# SlaveV1.net
KiCad netlist of a schematic drawn in EAGLE
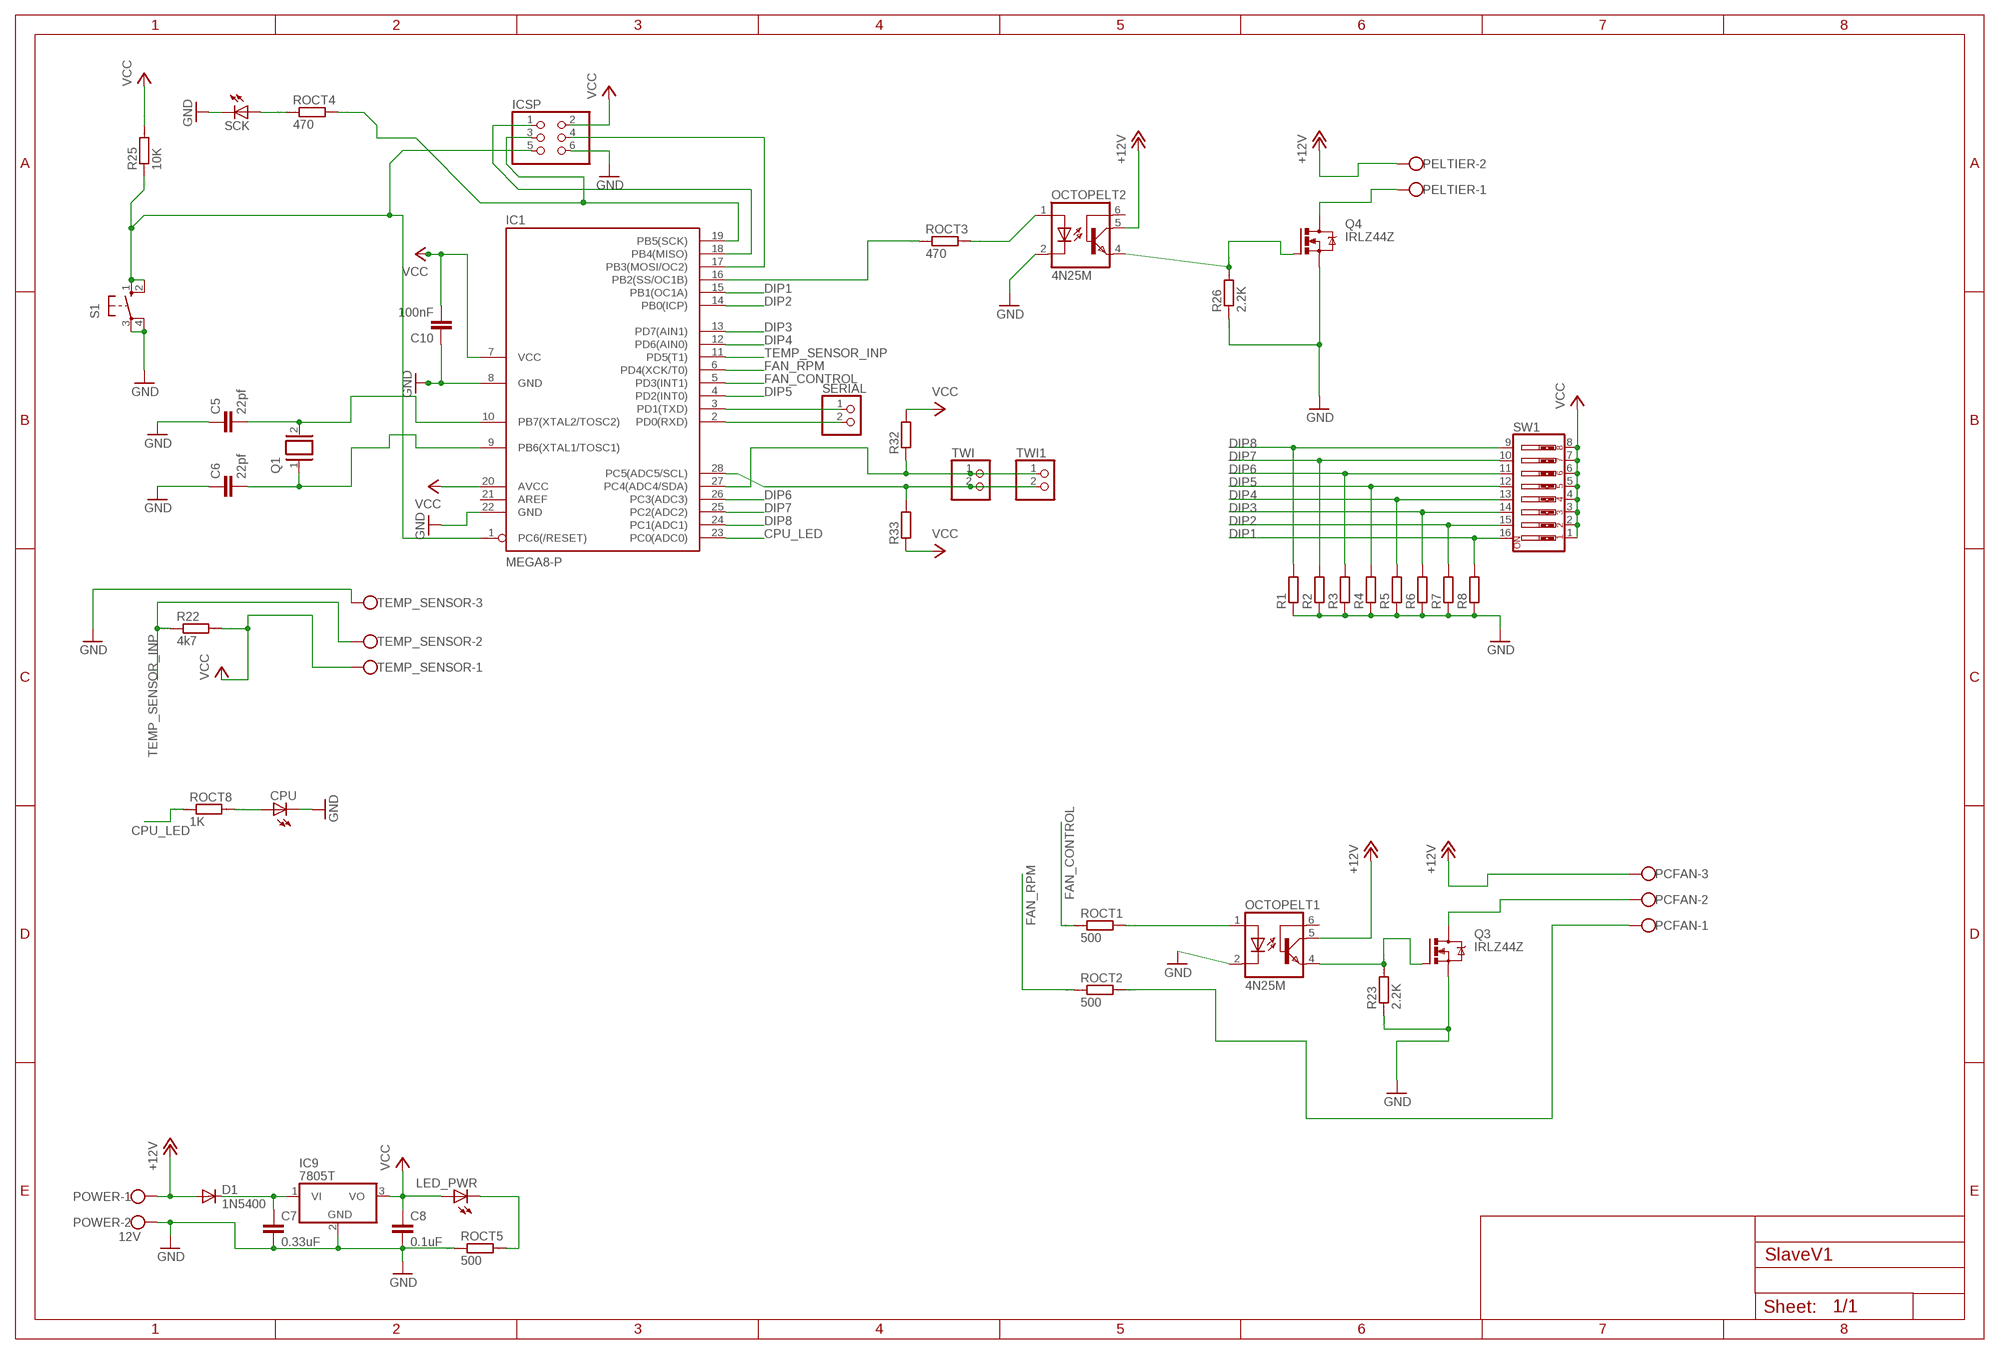
[diagram p0: schematic, sheet 1]

(export (version "E")
  (design (tool "Eeschema 10.0.6"))
  (components
    (comp (ref "C5")
      (value "22pf")
      (footprint "eagle-import:C2.5-3")
      (libsource (lib "eagle-import") (part "C2,5-3"))
    )
    (comp (ref "C6")
      (value "22pf")
      (footprint "eagle-import:C2.5-3")
      (libsource (lib "eagle-import") (part "C2,5-3"))
    )
    (comp (ref "C7")
      (value "0.33uF")
      (footprint "eagle-import:C2.5-3")
      (libsource (lib "eagle-import") (part "C2,5-3"))
    )
    (comp (ref "C8")
      (value "0.1uF")
      (footprint "eagle-import:C2.5-3")
      (libsource (lib "eagle-import") (part "C2,5-3"))
    )
    (comp (ref "C10")
      (value "100nF")
      (footprint "eagle-import:C2.5-3")
      (libsource (lib "eagle-import") (part "C2,5-3"))
    )
    (comp (ref "CPU")
      (value "LED5MM")
      (footprint "eagle-import:LED5MM")
      (libsource (lib "eagle-import") (part "LED5MM"))
    )
    (comp (ref "D1")
      (value "1N5400")
      (footprint "eagle-import:DO201-15")
      (libsource (lib "eagle-import") (part "1N5400"))
    )
    (comp (ref "IC1")
      (value "MEGA8-P")
      (footprint "eagle-import:DIL28-3")
      (libsource (lib "eagle-import") (part "MEGA8-P"))
    )
    (comp (ref "IC9")
      (value "7805T")
      (footprint "eagle-import:TO220H")
      (libsource (lib "eagle-import") (part "78T05"))
    )
    (comp (ref "ICSP")
      (value "PINHD-2X3")
      (footprint "eagle-import:2X03")
      (libsource (lib "eagle-import") (part "PINHD-2X3"))
    )
    (comp (ref "LED_PWR")
      (value "LED5MM")
      (footprint "eagle-import:LED5MM")
      (libsource (lib "eagle-import") (part "LED5MM"))
    )
    (comp (ref "OCTOPELT1")
      (value "4N25M")
      (footprint "eagle-import:DIL06")
      (fields (field (name "MPN") "4N25-M"))
      (libsource (lib "eagle-import") (part "4N?M25"))
    )
    (comp (ref "OCTOPELT2")
      (value "4N25M")
      (footprint "eagle-import:DIL06")
      (fields (field (name "MPN") "4N25-M"))
      (libsource (lib "eagle-import") (part "4N?M25"))
    )
    (comp (ref "PCFAN")
      (value "W237-103")
      (footprint "eagle-import:W237-103")
      (fields (field (name "MPN") "237-103"))
      (libsource (lib "eagle-import") (part "W237-103"))
    )
    (comp (ref "PELTIER")
      (value "W237-102")
      (footprint "eagle-import:W237-102")
      (fields (field (name "MPN") "237-102"))
      (libsource (lib "eagle-import") (part "W237-102"))
    )
    (comp (ref "POWER")
      (value "12V")
      (footprint "eagle-import:W237-102")
      (fields (field (name "MPN") "237-102"))
      (libsource (lib "eagle-import") (part "W237-102"))
    )
    (comp (ref "Q1")
      (value "XTAL")
      (footprint "eagle-import:Q")
      (libsource (lib "eagle-import") (part "XTAL"))
    )
    (comp (ref "Q3")
      (value "IRLZ44Z")
      (footprint "eagle-import:TO220BH")
      (libsource (lib "eagle-import") (part "IRLZ44Z"))
    )
    (comp (ref "Q4")
      (value "IRLZ44Z")
      (footprint "eagle-import:TO220BH")
      (libsource (lib "eagle-import") (part "IRLZ44Z"))
    )
    (comp (ref "R1")
      (value "R-EU_0207/10")
      (footprint "eagle-import:0207_10")
      (libsource (lib "eagle-import") (part "R-EU_0207/10"))
    )
    (comp (ref "R2")
      (value "R-EU_0207/10")
      (footprint "eagle-import:0207_10")
      (libsource (lib "eagle-import") (part "R-EU_0207/10"))
    )
    (comp (ref "R3")
      (value "R-EU_0207/10")
      (footprint "eagle-import:0207_10")
      (libsource (lib "eagle-import") (part "R-EU_0207/10"))
    )
    (comp (ref "R4")
      (value "R-EU_0207/10")
      (footprint "eagle-import:0207_10")
      (libsource (lib "eagle-import") (part "R-EU_0207/10"))
    )
    (comp (ref "R5")
      (value "R-EU_0207/10")
      (footprint "eagle-import:0207_10")
      (libsource (lib "eagle-import") (part "R-EU_0207/10"))
    )
    (comp (ref "R6")
      (value "R-EU_0207/10")
      (footprint "eagle-import:0207_10")
      (libsource (lib "eagle-import") (part "R-EU_0207/10"))
    )
    (comp (ref "R7")
      (value "R-EU_0207/10")
      (footprint "eagle-import:0207_10")
      (libsource (lib "eagle-import") (part "R-EU_0207/10"))
    )
    (comp (ref "R8")
      (value "R-EU_0207/10")
      (footprint "eagle-import:0207_10")
      (libsource (lib "eagle-import") (part "R-EU_0207/10"))
    )
    (comp (ref "R22")
      (value "4k7")
      (footprint "eagle-import:0204_7")
      (libsource (lib "eagle-import") (part "R0204/7"))
    )
    (comp (ref "R23")
      (value "2.2K")
      (footprint "eagle-import:0204_7")
      (libsource (lib "eagle-import") (part "R0204/7"))
    )
    (comp (ref "R25")
      (value "10K")
      (footprint "eagle-import:0204_7")
      (libsource (lib "eagle-import") (part "R0204/7"))
    )
    (comp (ref "R26")
      (value "2.2K")
      (footprint "eagle-import:0204_7")
      (libsource (lib "eagle-import") (part "R0204/7"))
    )
    (comp (ref "R32")
      (value "R-EU_0207/10")
      (footprint "eagle-import:0207_10")
      (libsource (lib "eagle-import") (part "R-EU_0207/10"))
    )
    (comp (ref "R33")
      (value "R-EU_0207/10")
      (footprint "eagle-import:0207_10")
      (libsource (lib "eagle-import") (part "R-EU_0207/10"))
    )
    (comp (ref "ROCT1")
      (value "500")
      (footprint "eagle-import:0204_7")
      (libsource (lib "eagle-import") (part "R0204/7"))
    )
    (comp (ref "ROCT2")
      (value "500")
      (footprint "eagle-import:0204_7")
      (libsource (lib "eagle-import") (part "R0204/7"))
    )
    (comp (ref "ROCT3")
      (value "470")
      (footprint "eagle-import:0204_7")
      (libsource (lib "eagle-import") (part "R0204/7"))
    )
    (comp (ref "ROCT4")
      (value "470")
      (footprint "eagle-import:0204_7")
      (libsource (lib "eagle-import") (part "R0204/7"))
    )
    (comp (ref "ROCT5")
      (value "500")
      (footprint "eagle-import:0204_7")
      (libsource (lib "eagle-import") (part "R0204/7"))
    )
    (comp (ref "ROCT8")
      (value "1K")
      (footprint "eagle-import:0204_7")
      (libsource (lib "eagle-import") (part "R0204/7"))
    )
    (comp (ref "S1")
      (value "10-XX")
      (footprint "eagle-import:B3F-10XX")
      (fields (field (name "MPN") "B3F-1000"))
      (libsource (lib "eagle-import") (part "10-XX"))
    )
    (comp (ref "SCK")
      (value "LED5MM")
      (footprint "eagle-import:LED5MM")
      (libsource (lib "eagle-import") (part "LED5MM"))
    )
    (comp (ref "SERIAL")
      (value "PINHD-1X2/90")
      (footprint "eagle-import:1X02_90")
      (libsource (lib "eagle-import") (part "PINHD-1X2/90"))
    )
    (comp (ref "SW1")
      (value "SW_DIP-8")
      (footprint "eagle-import:EDG-08")
      (libsource (lib "eagle-import") (part "SW_DIP-8"))
    )
    (comp (ref "TEMP_SENSOR")
      (value "W237-103")
      (footprint "eagle-import:W237-103")
      (fields (field (name "MPN") "237-103"))
      (libsource (lib "eagle-import") (part "W237-103"))
    )
    (comp (ref "TWI")
      (value "PINHD-1X2/90")
      (footprint "eagle-import:1X02_90")
      (libsource (lib "eagle-import") (part "PINHD-1X2/90"))
    )
    (comp (ref "TWI1")
      (value "PINHD-1X2/90")
      (footprint "eagle-import:1X02_90")
      (libsource (lib "eagle-import") (part "PINHD-1X2/90"))
    )
  )
  (nets
    (net (code "1") (name "+12V") (class "Default")
      (node (ref "D1") (pin "A") (pinfunction "A_A") (pintype "passive"))
      (node (ref "OCTOPELT1") (pin "5") (pinfunction "COL_5") (pintype "passive"))
      (node (ref "OCTOPELT2") (pin "5") (pinfunction "COL_5") (pintype "passive"))
      (node (ref "PCFAN") (pin "3") (pinfunction "KL_3") (pintype "passive"))
      (node (ref "PELTIER") (pin "2") (pinfunction "KL_2") (pintype "passive"))
      (node (ref "POWER") (pin "1") (pinfunction "KL_1") (pintype "passive"))
    )
    (net (code "2") (name "/CPU_LED") (class "Default")
      (node (ref "IC1") (pin "23") (pinfunction "PC0(ADC0)_23") (pintype "bidirectional"))
      (node (ref "ROCT8") (pin "1") (pinfunction "1_1") (pintype "passive"))
    )
    (net (code "3") (name "/DIP1") (class "Default")
      (node (ref "IC1") (pin "15") (pinfunction "PB1(OC1A)_15") (pintype "bidirectional"))
      (node (ref "R8") (pin "2") (pinfunction "2_2") (pintype "passive"))
      (node (ref "SW1") (pin "16") (pinfunction "16_16") (pintype "passive"))
    )
    (net (code "4") (name "/DIP2") (class "Default")
      (node (ref "IC1") (pin "14") (pinfunction "PB0(ICP)_14") (pintype "bidirectional"))
      (node (ref "R7") (pin "2") (pinfunction "2_2") (pintype "passive"))
      (node (ref "SW1") (pin "15") (pinfunction "15_15") (pintype "passive"))
    )
    (net (code "5") (name "/DIP3") (class "Default")
      (node (ref "IC1") (pin "13") (pinfunction "PD7(AIN1)_13") (pintype "bidirectional"))
      (node (ref "R6") (pin "2") (pinfunction "2_2") (pintype "passive"))
      (node (ref "SW1") (pin "14") (pinfunction "14_14") (pintype "passive"))
    )
    (net (code "6") (name "/DIP4") (class "Default")
      (node (ref "IC1") (pin "12") (pinfunction "PD6(AIN0)_12") (pintype "bidirectional"))
      (node (ref "R5") (pin "2") (pinfunction "2_2") (pintype "passive"))
      (node (ref "SW1") (pin "13") (pinfunction "13_13") (pintype "passive"))
    )
    (net (code "7") (name "/DIP5") (class "Default")
      (node (ref "IC1") (pin "4") (pinfunction "PD2(INT0)_4") (pintype "bidirectional"))
      (node (ref "R4") (pin "2") (pinfunction "2_2") (pintype "passive"))
      (node (ref "SW1") (pin "12") (pinfunction "12_12") (pintype "passive"))
    )
    (net (code "8") (name "/DIP6") (class "Default")
      (node (ref "IC1") (pin "26") (pinfunction "PC3(ADC3)_26") (pintype "bidirectional"))
      (node (ref "R3") (pin "2") (pinfunction "2_2") (pintype "passive"))
      (node (ref "SW1") (pin "11") (pinfunction "11_11") (pintype "passive"))
    )
    (net (code "9") (name "/DIP7") (class "Default")
      (node (ref "IC1") (pin "25") (pinfunction "PC2(ADC2)_25") (pintype "bidirectional"))
      (node (ref "R2") (pin "2") (pinfunction "2_2") (pintype "passive"))
      (node (ref "SW1") (pin "10") (pinfunction "10_10") (pintype "passive"))
    )
    (net (code "10") (name "/DIP8") (class "Default")
      (node (ref "IC1") (pin "24") (pinfunction "PC1(ADC1)_24") (pintype "bidirectional"))
      (node (ref "R1") (pin "2") (pinfunction "2_2") (pintype "passive"))
      (node (ref "SW1") (pin "9") (pinfunction "9_9") (pintype "passive"))
    )
    (net (code "11") (name "/FAN_CONTROL") (class "Default")
      (node (ref "IC1") (pin "5") (pinfunction "PD3(INT1)_5") (pintype "bidirectional"))
      (node (ref "ROCT1") (pin "1") (pinfunction "1_1") (pintype "passive"))
    )
    (net (code "12") (name "/FAN_RPM") (class "Default")
      (node (ref "IC1") (pin "6") (pinfunction "PD4(XCK/T0)_6") (pintype "bidirectional"))
      (node (ref "ROCT2") (pin "1") (pinfunction "1_1") (pintype "passive"))
    )
    (net (code "13") (name "/TEMP_SENSOR_INP") (class "Default")
      (node (ref "IC1") (pin "11") (pinfunction "PD5(T1)_11") (pintype "bidirectional"))
      (node (ref "R22") (pin "1") (pinfunction "1_1") (pintype "passive"))
      (node (ref "TEMP_SENSOR") (pin "2") (pinfunction "KL_2") (pintype "passive"))
    )
    (net (code "14") (name "GND") (class "Default")
      (node (ref "C10") (pin "1") (pinfunction "1_1") (pintype "passive"))
      (node (ref "C5") (pin "1") (pinfunction "1_1") (pintype "passive"))
      (node (ref "C6") (pin "1") (pinfunction "1_1") (pintype "passive"))
      (node (ref "C7") (pin "2") (pinfunction "2_2") (pintype "passive"))
      (node (ref "C8") (pin "2") (pinfunction "2_2") (pintype "passive"))
      (node (ref "CPU") (pin "K") (pinfunction "C_K") (pintype "passive"))
      (node (ref "IC1") (pin "22") (pinfunction "GND_22") (pintype "power_in"))
      (node (ref "IC1") (pin "8") (pinfunction "GND_8") (pintype "power_in"))
      (node (ref "IC9") (pin "2") (pinfunction "GND_2") (pintype "passive"))
      (node (ref "ICSP") (pin "6") (pinfunction "6_6") (pintype "passive"))
      (node (ref "OCTOPELT1") (pin "2") (pinfunction "C_2") (pintype "passive"))
      (node (ref "OCTOPELT2") (pin "2") (pinfunction "C_2") (pintype "passive"))
      (node (ref "POWER") (pin "2") (pinfunction "KL_2") (pintype "passive"))
      (node (ref "Q3") (pin "S") (pinfunction "S_S") (pintype "passive"))
      (node (ref "Q4") (pin "S") (pinfunction "S_S") (pintype "passive"))
      (node (ref "R1") (pin "1") (pinfunction "1_1") (pintype "passive"))
      (node (ref "R2") (pin "1") (pinfunction "1_1") (pintype "passive"))
      (node (ref "R23") (pin "1") (pinfunction "1_1") (pintype "passive"))
      (node (ref "R26") (pin "1") (pinfunction "1_1") (pintype "passive"))
      (node (ref "R3") (pin "1") (pinfunction "1_1") (pintype "passive"))
      (node (ref "R4") (pin "1") (pinfunction "1_1") (pintype "passive"))
      (node (ref "R5") (pin "1") (pinfunction "1_1") (pintype "passive"))
      (node (ref "R6") (pin "1") (pinfunction "1_1") (pintype "passive"))
      (node (ref "R7") (pin "1") (pinfunction "1_1") (pintype "passive"))
      (node (ref "R8") (pin "1") (pinfunction "1_1") (pintype "passive"))
      (node (ref "ROCT5") (pin "1") (pinfunction "1_1") (pintype "passive"))
      (node (ref "S1") (pin "3") (pinfunction "P_3") (pintype "passive"))
      (node (ref "S1") (pin "4") (pinfunction "P1_4") (pintype "passive"))
      (node (ref "SCK") (pin "K") (pinfunction "C_K") (pintype "passive"))
      (node (ref "TEMP_SENSOR") (pin "3") (pinfunction "KL_3") (pintype "passive"))
    )
    (net (code "15") (name "Net-(CPU-PadA)") (class "Default")
      (node (ref "CPU") (pin "A") (pinfunction "A_A") (pintype "passive"))
      (node (ref "ROCT8") (pin "2") (pinfunction "2_2") (pintype "passive"))
    )
    (net (code "16") (name "Net-(IC1-PB2(SS{slash}OC1B))") (class "Default")
      (node (ref "IC1") (pin "16") (pinfunction "PB2(SS/OC1B)_16") (pintype "bidirectional"))
      (node (ref "ROCT3") (pin "1") (pinfunction "1_1") (pintype "passive"))
    )
    (net (code "17") (name "Net-(IC1-PB3(MOSI{slash}OC2))") (class "Default")
      (node (ref "IC1") (pin "17") (pinfunction "PB3(MOSI/OC2)_17") (pintype "bidirectional"))
      (node (ref "ICSP") (pin "4") (pinfunction "4_4") (pintype "passive"))
    )
    (net (code "18") (name "Net-(IC1-PB4(MISO))") (class "Default")
      (node (ref "IC1") (pin "18") (pinfunction "PB4(MISO)_18") (pintype "bidirectional"))
      (node (ref "ICSP") (pin "1") (pinfunction "1_1") (pintype "passive"))
    )
    (net (code "19") (name "Net-(IC1-PB5(SCK))") (class "Default")
      (node (ref "IC1") (pin "19") (pinfunction "PB5(SCK)_19") (pintype "bidirectional"))
      (node (ref "ICSP") (pin "3") (pinfunction "3_3") (pintype "passive"))
      (node (ref "ROCT4") (pin "2") (pinfunction "2_2") (pintype "passive"))
    )
    (net (code "20") (name "Net-(IC1-PB6(XTAL1{slash}TOSC1))") (class "Default")
      (node (ref "C6") (pin "2") (pinfunction "2_2") (pintype "passive"))
      (node (ref "IC1") (pin "9") (pinfunction "PB6(XTAL1/TOSC1)_9") (pintype "bidirectional"))
      (node (ref "Q1") (pin "1") (pinfunction "1_1") (pintype "passive"))
    )
    (net (code "21") (name "Net-(IC1-PB7(XTAL2{slash}TOSC2))") (class "Default")
      (node (ref "C5") (pin "2") (pinfunction "2_2") (pintype "passive"))
      (node (ref "IC1") (pin "10") (pinfunction "PB7(XTAL2/TOSC2)_10") (pintype "bidirectional"))
      (node (ref "Q1") (pin "2") (pinfunction "2_2") (pintype "passive"))
    )
    (net (code "22") (name "Net-(IC1-PC4(ADC4{slash}SDA))") (class "Default")
      (node (ref "IC1") (pin "27") (pinfunction "PC4(ADC4/SDA)_27") (pintype "bidirectional"))
      (node (ref "R32") (pin "1") (pinfunction "1_1") (pintype "passive"))
      (node (ref "TWI") (pin "1") (pinfunction "1_1") (pintype "passive"))
      (node (ref "TWI1") (pin "1") (pinfunction "1_1") (pintype "passive"))
    )
    (net (code "23") (name "Net-(IC1-PC5(ADC5{slash}SCL))") (class "Default")
      (node (ref "IC1") (pin "28") (pinfunction "PC5(ADC5/SCL)_28") (pintype "bidirectional"))
      (node (ref "R33") (pin "2") (pinfunction "2_2") (pintype "passive"))
      (node (ref "TWI") (pin "2") (pinfunction "2_2") (pintype "passive"))
      (node (ref "TWI1") (pin "2") (pinfunction "2_2") (pintype "passive"))
    )
    (net (code "24") (name "Net-(IC1-PC6({slash}RESET))") (class "Default")
      (node (ref "IC1") (pin "1") (pinfunction "PC6(/RESET)_1") (pintype "bidirectional"))
      (node (ref "ICSP") (pin "5") (pinfunction "5_5") (pintype "passive"))
      (node (ref "R25") (pin "1") (pinfunction "1_1") (pintype "passive"))
      (node (ref "S1") (pin "1") (pinfunction "S_1") (pintype "passive"))
      (node (ref "S1") (pin "2") (pinfunction "S1_2") (pintype "passive"))
    )
    (net (code "25") (name "Net-(IC1-PD0(RXD))") (class "Default")
      (node (ref "IC1") (pin "2") (pinfunction "PD0(RXD)_2") (pintype "bidirectional"))
      (node (ref "SERIAL") (pin "2") (pinfunction "2_2") (pintype "passive"))
    )
    (net (code "26") (name "Net-(IC1-PD1(TXD))") (class "Default")
      (node (ref "IC1") (pin "3") (pinfunction "PD1(TXD)_3") (pintype "bidirectional"))
      (node (ref "SERIAL") (pin "1") (pinfunction "1_1") (pintype "passive"))
    )
    (net (code "27") (name "Net-(IC9-VI)") (class "Default")
      (node (ref "C7") (pin "1") (pinfunction "1_1") (pintype "passive"))
      (node (ref "D1") (pin "C") (pinfunction "C_C") (pintype "passive"))
      (node (ref "IC9") (pin "1") (pinfunction "VI_1") (pintype "input"))
    )
    (net (code "28") (name "Net-(LED_PWR-C)") (class "Default")
      (node (ref "LED_PWR") (pin "K") (pinfunction "C_K") (pintype "passive"))
      (node (ref "ROCT5") (pin "2") (pinfunction "2_2") (pintype "passive"))
    )
    (net (code "29") (name "Net-(OCTOPELT1-A)") (class "Default")
      (node (ref "OCTOPELT1") (pin "1") (pinfunction "A_1") (pintype "passive"))
      (node (ref "ROCT1") (pin "2") (pinfunction "2_2") (pintype "passive"))
    )
    (net (code "30") (name "Net-(OCTOPELT1-EMI)") (class "Default")
      (node (ref "OCTOPELT1") (pin "4") (pinfunction "EMI_4") (pintype "passive"))
      (node (ref "Q3") (pin "G") (pinfunction "G_G") (pintype "passive"))
      (node (ref "R23") (pin "2") (pinfunction "2_2") (pintype "passive"))
    )
    (net (code "31") (name "Net-(OCTOPELT2-A)") (class "Default")
      (node (ref "OCTOPELT2") (pin "1") (pinfunction "A_1") (pintype "passive"))
      (node (ref "ROCT3") (pin "2") (pinfunction "2_2") (pintype "passive"))
    )
    (net (code "32") (name "Net-(OCTOPELT2-EMI)") (class "Default")
      (node (ref "OCTOPELT2") (pin "4") (pinfunction "EMI_4") (pintype "passive"))
      (node (ref "Q4") (pin "G") (pinfunction "G_G") (pintype "passive"))
      (node (ref "R26") (pin "2") (pinfunction "2_2") (pintype "passive"))
    )
    (net (code "33") (name "Net-(PCFANA-KL)") (class "Default")
      (node (ref "PCFAN") (pin "1") (pinfunction "KL_1") (pintype "passive"))
      (node (ref "ROCT2") (pin "2") (pinfunction "2_2") (pintype "passive"))
    )
    (net (code "34") (name "Net-(PCFANB-KL)") (class "Default")
      (node (ref "PCFAN") (pin "2") (pinfunction "KL_2") (pintype "passive"))
      (node (ref "Q3") (pin "D") (pinfunction "D_D") (pintype "passive"))
    )
    (net (code "35") (name "Net-(PELTIERA-KL)") (class "Default")
      (node (ref "PELTIER") (pin "1") (pinfunction "KL_1") (pintype "passive"))
      (node (ref "Q4") (pin "D") (pinfunction "D_D") (pintype "passive"))
    )
    (net (code "36") (name "Net-(ROCT4-Pad1)") (class "Default")
      (node (ref "ROCT4") (pin "1") (pinfunction "1_1") (pintype "passive"))
      (node (ref "SCK") (pin "A") (pinfunction "A_A") (pintype "passive"))
    )
    (net (code "37") (name "VCC") (class "Default")
      (node (ref "C10") (pin "2") (pinfunction "2_2") (pintype "passive"))
      (node (ref "C8") (pin "1") (pinfunction "1_1") (pintype "passive"))
      (node (ref "IC1") (pin "20") (pinfunction "AVCC_20") (pintype "power_in"))
      (node (ref "IC1") (pin "7") (pinfunction "VCC_7") (pintype "power_in"))
      (node (ref "IC9") (pin "3") (pinfunction "VO_3") (pintype "passive"))
      (node (ref "ICSP") (pin "2") (pinfunction "2_2") (pintype "passive"))
      (node (ref "LED_PWR") (pin "A") (pinfunction "A_A") (pintype "passive"))
      (node (ref "R22") (pin "2") (pinfunction "2_2") (pintype "passive"))
      (node (ref "R25") (pin "2") (pinfunction "2_2") (pintype "passive"))
      (node (ref "R32") (pin "2") (pinfunction "2_2") (pintype "passive"))
      (node (ref "R33") (pin "1") (pinfunction "1_1") (pintype "passive"))
      (node (ref "SW1") (pin "1") (pinfunction "1_1") (pintype "passive"))
      (node (ref "SW1") (pin "2") (pinfunction "2_2") (pintype "passive"))
      (node (ref "SW1") (pin "3") (pinfunction "3_3") (pintype "passive"))
      (node (ref "SW1") (pin "4") (pinfunction "4_4") (pintype "passive"))
      (node (ref "SW1") (pin "5") (pinfunction "5_5") (pintype "passive"))
      (node (ref "SW1") (pin "6") (pinfunction "6_6") (pintype "passive"))
      (node (ref "SW1") (pin "7") (pinfunction "7_7") (pintype "passive"))
      (node (ref "SW1") (pin "8") (pinfunction "8_8") (pintype "passive"))
      (node (ref "TEMP_SENSOR") (pin "1") (pinfunction "KL_1") (pintype "passive"))
    )
    (net (code "38") (name "unconnected-(IC1-AREF-Pad21)") (class "Default")
      (node (ref "IC1") (pin "21") (pinfunction "AREF_21") (pintype "passive"))
    )
    (net (code "39") (name "unconnected-(OCTOPELT1-BAS-Pad6)") (class "Default")
      (node (ref "OCTOPELT1") (pin "6") (pinfunction "BAS_6") (pintype "passive"))
    )
    (net (code "40") (name "unconnected-(OCTOPELT2-BAS-Pad6)") (class "Default")
      (node (ref "OCTOPELT2") (pin "6") (pinfunction "BAS_6") (pintype "passive"))
    )
  )
)
